# midi-vidi.net
KiCad netlist of a schematic drawn in EAGLE
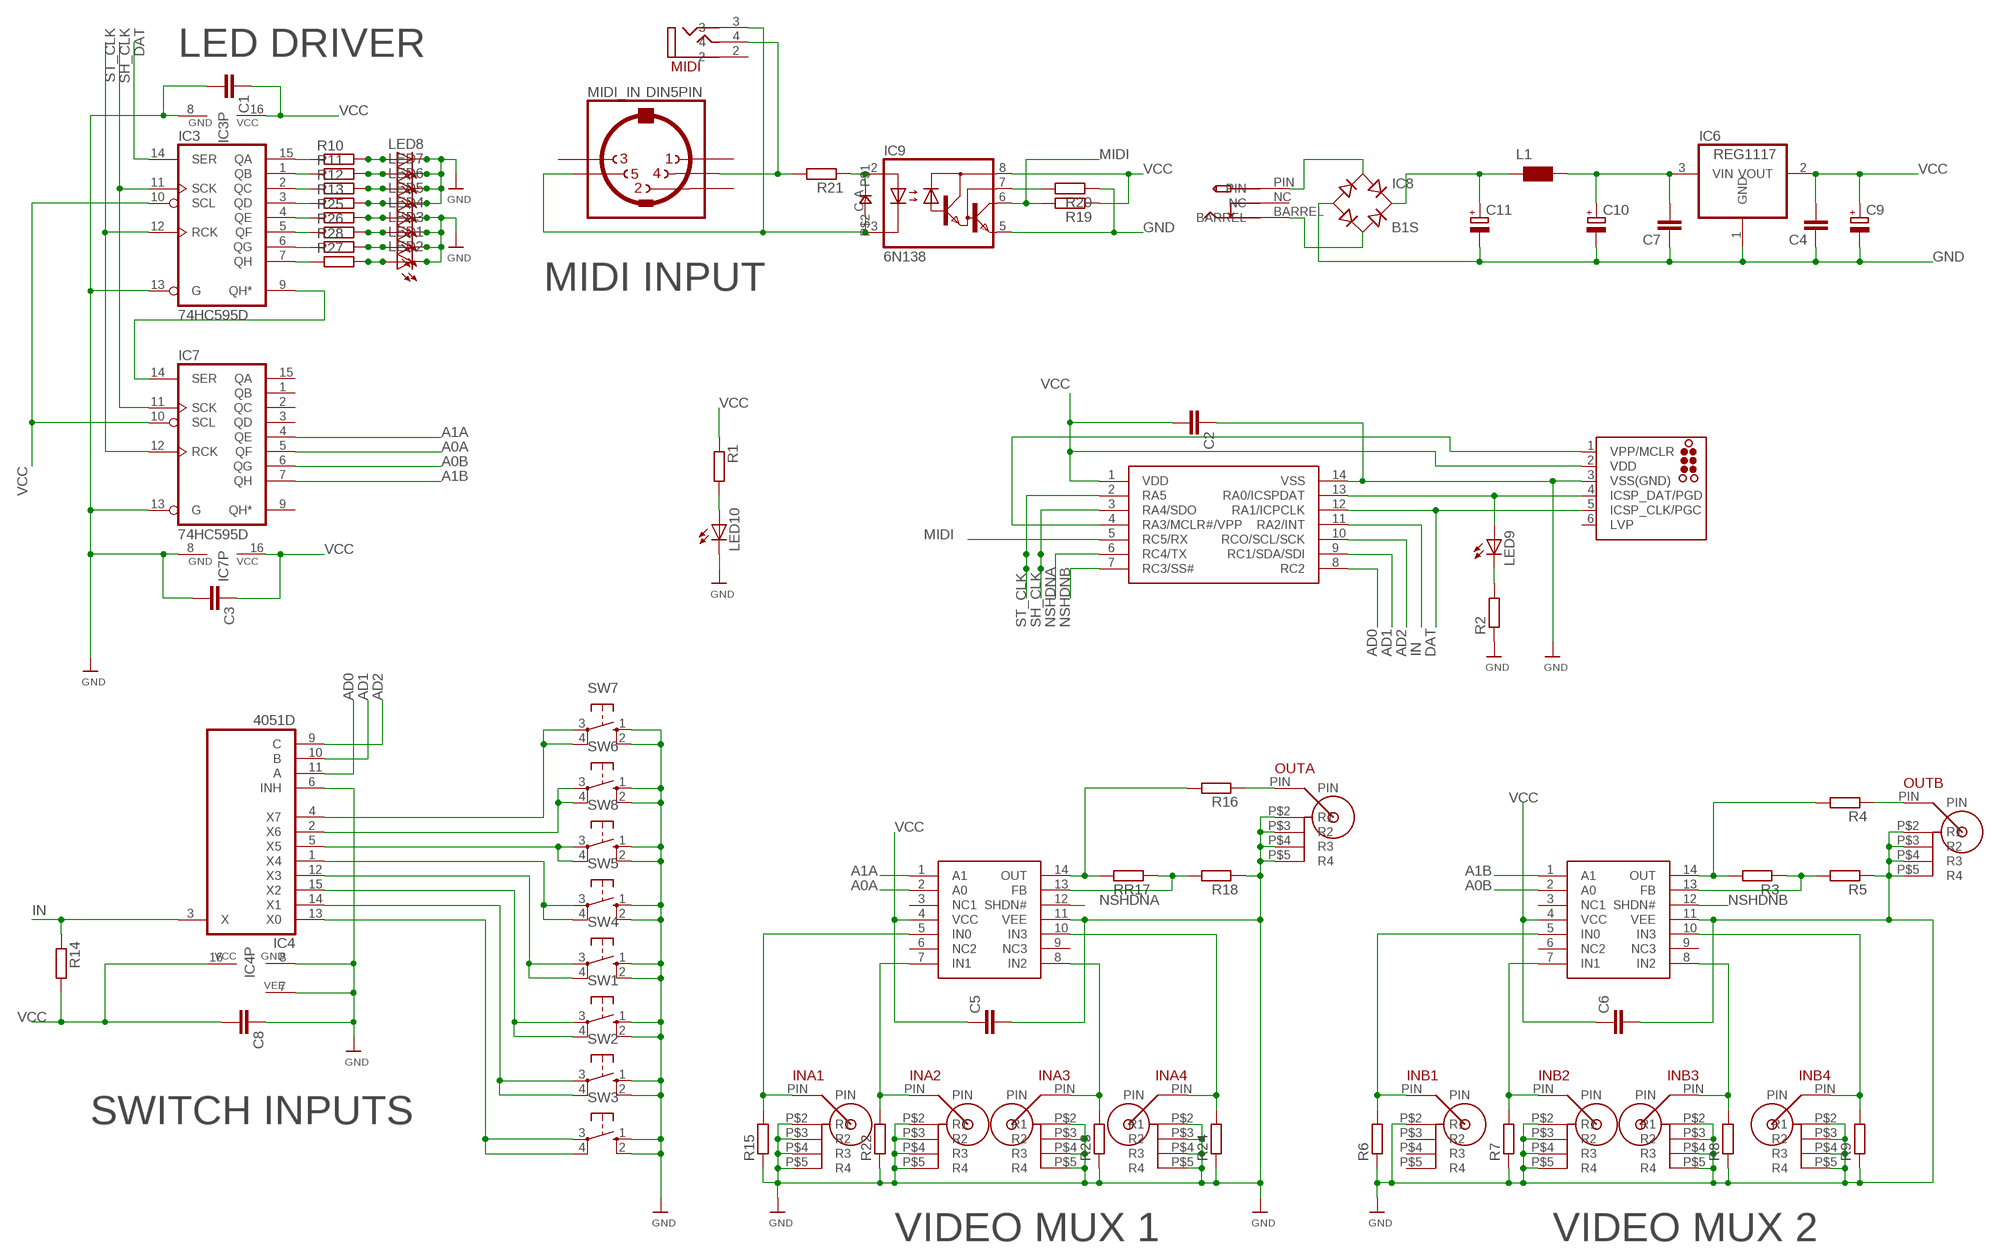
[diagram p0: schematic, sheet 1]

(export (version "E")
  (design (tool "Eeschema 10.0.6"))
  (components
    (comp (ref "C1")
      (value "C-EUC0805")
      (footprint "eagle-import:C0805")
      (libsource (lib "eagle-import") (part "C-EUC0805"))
    )
    (comp (ref "C2")
      (value "C-EUC0805")
      (footprint "eagle-import:C0805")
      (libsource (lib "eagle-import") (part "C-EUC0805"))
    )
    (comp (ref "C3")
      (value "C-EUC0805")
      (footprint "eagle-import:C0805")
      (libsource (lib "eagle-import") (part "C-EUC0805"))
    )
    (comp (ref "C4")
      (value "C-EUC0805")
      (footprint "eagle-import:C0805")
      (libsource (lib "eagle-import") (part "C-EUC0805"))
    )
    (comp (ref "C5")
      (value "C-EUC0805")
      (footprint "eagle-import:C0805")
      (libsource (lib "eagle-import") (part "C-EUC0805"))
    )
    (comp (ref "C6")
      (value "C-EUC0805")
      (footprint "eagle-import:C0805")
      (libsource (lib "eagle-import") (part "C-EUC0805"))
    )
    (comp (ref "C7")
      (value "C-EUC0805")
      (footprint "eagle-import:C0805")
      (libsource (lib "eagle-import") (part "C-EUC0805"))
    )
    (comp (ref "C8")
      (value "C-EUC0805")
      (footprint "eagle-import:C0805")
      (libsource (lib "eagle-import") (part "C-EUC0805"))
    )
    (comp (ref "C9")
      (value "CPOL-EUE2,5-6E")
      (footprint "eagle-import:E2,5-6E")
      (libsource (lib "eagle-import") (part "CPOL-EUE2,5-6E"))
    )
    (comp (ref "C10")
      (value "CPOL-EUE2,5-6E")
      (footprint "eagle-import:E2,5-6E")
      (libsource (lib "eagle-import") (part "CPOL-EUE2,5-6E"))
    )
    (comp (ref "C11")
      (value "CPOL-EUE2,5-6E")
      (footprint "eagle-import:E2,5-6E")
      (libsource (lib "eagle-import") (part "CPOL-EUE2,5-6E"))
    )
    (comp (ref "D1")
      (value "0805DIODE")
      (footprint "eagle-import:0805DIODE")
      (libsource (lib "eagle-import") (part "0805DIODE"))
    )
    (comp (ref "IC1")
      (value "MAX4311SO14")
      (footprint "eagle-import:SO14")
      (libsource (lib "eagle-import") (part "MAX4311SO14"))
    )
    (comp (ref "IC2")
      (value "PIC16F1825SO14")
      (footprint "eagle-import:SO14")
      (libsource (lib "eagle-import") (part "PIC16F1825SO14"))
    )
    (comp (ref "IC3")
      (value "74HC595D")
      (footprint "eagle-import:SO16")
      (libsource (lib "eagle-import") (part "74595DHC"))
    )
    (comp (ref "IC4")
      (value "4051D")
      (footprint "eagle-import:SO16")
      (libsource (lib "eagle-import") (part "4051D"))
    )
    (comp (ref "IC5")
      (value "MAX4311SO14")
      (footprint "eagle-import:SO14")
      (libsource (lib "eagle-import") (part "MAX4311SO14"))
    )
    (comp (ref "IC6")
      (value "REG1117")
      (footprint "eagle-import:SOT223")
      (libsource (lib "eagle-import") (part "REG1117"))
    )
    (comp (ref "IC7")
      (value "74HC595D")
      (footprint "eagle-import:SO16")
      (libsource (lib "eagle-import") (part "74595DHC"))
    )
    (comp (ref "IC8")
      (value "B1S")
      (footprint "eagle-import:MBS")
      (libsource (lib "eagle-import") (part "BS1"))
    )
    (comp (ref "IC9")
      (value "6N138")
      (footprint "eagle-import:DIL08")
      (fields (field (name "MF") "VISHAY/TELEFUNKEN"))
      (libsource (lib "eagle-import") (part "6N138"))
    )
    (comp (ref "ICSP")
      (value "TC2030-MCP-NL")
      (footprint "eagle-import:TC2030-MCP-NL")
      (libsource (lib "eagle-import") (part "TC2030-MCP-NL"))
    )
    (comp (ref "INA1")
      (value "RCAVERT")
      (footprint "eagle-import:RCAVERT")
      (libsource (lib "eagle-import") (part "RCAVERT"))
    )
    (comp (ref "INA2")
      (value "RCAVERT")
      (footprint "eagle-import:RCAVERT")
      (libsource (lib "eagle-import") (part "RCAVERT"))
    )
    (comp (ref "INA3")
      (value "RCAVERT")
      (footprint "eagle-import:RCAVERT")
      (libsource (lib "eagle-import") (part "RCAVERT"))
    )
    (comp (ref "INA4")
      (value "RCAVERT")
      (footprint "eagle-import:RCAVERT")
      (libsource (lib "eagle-import") (part "RCAVERT"))
    )
    (comp (ref "INB1")
      (value "RCAVERT")
      (footprint "eagle-import:RCAVERT")
      (libsource (lib "eagle-import") (part "RCAVERT"))
    )
    (comp (ref "INB2")
      (value "RCAVERT")
      (footprint "eagle-import:RCAVERT")
      (libsource (lib "eagle-import") (part "RCAVERT"))
    )
    (comp (ref "INB3")
      (value "RCAVERT")
      (footprint "eagle-import:RCAVERT")
      (libsource (lib "eagle-import") (part "RCAVERT"))
    )
    (comp (ref "INB4")
      (value "RCAVERT")
      (footprint "eagle-import:RCAVERT")
      (libsource (lib "eagle-import") (part "RCAVERT"))
    )
    (comp (ref "L1")
      (value "WE-TI_L")
      (footprint "eagle-import:WE-TI_L")
      (libsource (lib "eagle-import") (part "WE-TI_L"))
    )
    (comp (ref "LED1")
      (value "LED3MM")
      (footprint "eagle-import:LED3MM")
      (libsource (lib "eagle-import") (part "LED3MM"))
    )
    (comp (ref "LED2")
      (value "LED3MM")
      (footprint "eagle-import:LED3MM")
      (libsource (lib "eagle-import") (part "LED3MM"))
    )
    (comp (ref "LED3")
      (value "LED3MM")
      (footprint "eagle-import:LED3MM")
      (libsource (lib "eagle-import") (part "LED3MM"))
    )
    (comp (ref "LED4")
      (value "LED3MM")
      (footprint "eagle-import:LED3MM")
      (libsource (lib "eagle-import") (part "LED3MM"))
    )
    (comp (ref "LED5")
      (value "LED3MM")
      (footprint "eagle-import:LED3MM")
      (libsource (lib "eagle-import") (part "LED3MM"))
    )
    (comp (ref "LED6")
      (value "LED3MM")
      (footprint "eagle-import:LED3MM")
      (libsource (lib "eagle-import") (part "LED3MM"))
    )
    (comp (ref "LED7")
      (value "LED3MM")
      (footprint "eagle-import:LED3MM")
      (libsource (lib "eagle-import") (part "LED3MM"))
    )
    (comp (ref "LED8")
      (value "LED3MM")
      (footprint "eagle-import:LED3MM")
      (libsource (lib "eagle-import") (part "LED3MM"))
    )
    (comp (ref "LED9")
      (value "LED3MM")
      (footprint "eagle-import:LED3MM")
      (libsource (lib "eagle-import") (part "LED3MM"))
    )
    (comp (ref "LED10")
      (value "LED3MM")
      (footprint "eagle-import:LED3MM")
      (libsource (lib "eagle-import") (part "LED3MM"))
    )
    (comp (ref "MIDI")
      (value "VERTICAL_3_5MM_SOCKET")
      (footprint "eagle-import:VERTICAL_3_5MM_SOCKET")
      (libsource (lib "eagle-import") (part "VERTICAL_3_5MM_SOCKET"))
    )
    (comp (ref "MIDI_IN")
      (value "DIN5PIN")
      (footprint "eagle-import:EDGEDIN")
      (libsource (lib "eagle-import") (part "DIN5PIN"))
    )
    (comp (ref "OUTA")
      (value "RCAVERT")
      (footprint "eagle-import:RCAVERT")
      (libsource (lib "eagle-import") (part "RCAVERT"))
    )
    (comp (ref "OUTB")
      (value "RCAVERT")
      (footprint "eagle-import:RCAVERT")
      (libsource (lib "eagle-import") (part "RCAVERT"))
    )
    (comp (ref "R1")
      (value "R-EU_R0805")
      (footprint "eagle-import:R0805")
      (libsource (lib "eagle-import") (part "R-EU_R0805"))
    )
    (comp (ref "R2")
      (value "R-EU_R0805")
      (footprint "eagle-import:R0805")
      (libsource (lib "eagle-import") (part "R-EU_R0805"))
    )
    (comp (ref "R3")
      (value "R-EU_R0805")
      (footprint "eagle-import:R0805")
      (libsource (lib "eagle-import") (part "R-EU_R0805"))
    )
    (comp (ref "R4")
      (value "R-EU_R0805")
      (footprint "eagle-import:R0805")
      (libsource (lib "eagle-import") (part "R-EU_R0805"))
    )
    (comp (ref "R5")
      (value "R-EU_R0805")
      (footprint "eagle-import:R0805")
      (libsource (lib "eagle-import") (part "R-EU_R0805"))
    )
    (comp (ref "R6")
      (value "R-EU_R0805")
      (footprint "eagle-import:R0805")
      (libsource (lib "eagle-import") (part "R-EU_R0805"))
    )
    (comp (ref "R7")
      (value "R-EU_R0805")
      (footprint "eagle-import:R0805")
      (libsource (lib "eagle-import") (part "R-EU_R0805"))
    )
    (comp (ref "R8")
      (value "R-EU_R0805")
      (footprint "eagle-import:R0805")
      (libsource (lib "eagle-import") (part "R-EU_R0805"))
    )
    (comp (ref "R9")
      (value "R-EU_R0805")
      (footprint "eagle-import:R0805")
      (libsource (lib "eagle-import") (part "R-EU_R0805"))
    )
    (comp (ref "R10")
      (value "R-EU_R0805")
      (footprint "eagle-import:R0805")
      (libsource (lib "eagle-import") (part "R-EU_R0805"))
    )
    (comp (ref "R11")
      (value "R-EU_R0805")
      (footprint "eagle-import:R0805")
      (libsource (lib "eagle-import") (part "R-EU_R0805"))
    )
    (comp (ref "R12")
      (value "R-EU_R0805")
      (footprint "eagle-import:R0805")
      (libsource (lib "eagle-import") (part "R-EU_R0805"))
    )
    (comp (ref "R13")
      (value "R-EU_R0805")
      (footprint "eagle-import:R0805")
      (libsource (lib "eagle-import") (part "R-EU_R0805"))
    )
    (comp (ref "R14")
      (value "R-EU_R0805")
      (footprint "eagle-import:R0805")
      (libsource (lib "eagle-import") (part "R-EU_R0805"))
    )
    (comp (ref "R15")
      (value "R-EU_R0805")
      (footprint "eagle-import:R0805")
      (libsource (lib "eagle-import") (part "R-EU_R0805"))
    )
    (comp (ref "R16")
      (value "R-EU_R0805")
      (footprint "eagle-import:R0805")
      (libsource (lib "eagle-import") (part "R-EU_R0805"))
    )
    (comp (ref "R18")
      (value "R-EU_R0805")
      (footprint "eagle-import:R0805")
      (libsource (lib "eagle-import") (part "R-EU_R0805"))
    )
    (comp (ref "R19")
      (value "R-EU_R0805")
      (footprint "eagle-import:R0805")
      (libsource (lib "eagle-import") (part "R-EU_R0805"))
    )
    (comp (ref "R20")
      (value "R-EU_R0805")
      (footprint "eagle-import:R0805")
      (libsource (lib "eagle-import") (part "R-EU_R0805"))
    )
    (comp (ref "R21")
      (value "R-EU_R0805")
      (footprint "eagle-import:R0805")
      (libsource (lib "eagle-import") (part "R-EU_R0805"))
    )
    (comp (ref "R22")
      (value "R-EU_R0805")
      (footprint "eagle-import:R0805")
      (libsource (lib "eagle-import") (part "R-EU_R0805"))
    )
    (comp (ref "R23")
      (value "R-EU_R0805")
      (footprint "eagle-import:R0805")
      (libsource (lib "eagle-import") (part "R-EU_R0805"))
    )
    (comp (ref "R24")
      (value "R-EU_R0805")
      (footprint "eagle-import:R0805")
      (libsource (lib "eagle-import") (part "R-EU_R0805"))
    )
    (comp (ref "R25")
      (value "R-EU_R0805")
      (footprint "eagle-import:R0805")
      (libsource (lib "eagle-import") (part "R-EU_R0805"))
    )
    (comp (ref "R26")
      (value "R-EU_R0805")
      (footprint "eagle-import:R0805")
      (libsource (lib "eagle-import") (part "R-EU_R0805"))
    )
    (comp (ref "R27")
      (value "R-EU_R0805")
      (footprint "eagle-import:R0805")
      (libsource (lib "eagle-import") (part "R-EU_R0805"))
    )
    (comp (ref "R28")
      (value "R-EU_R0805")
      (footprint "eagle-import:R0805")
      (libsource (lib "eagle-import") (part "R-EU_R0805"))
    )
    (comp (ref "RR17")
      (value "R-EU_R0805")
      (footprint "eagle-import:R0805")
      (libsource (lib "eagle-import") (part "R-EU_R0805"))
    )
    (comp (ref "SW1")
      (value "10-XX")
      (footprint "eagle-import:B3F-10XX")
      (fields (field (name "MPN") "B3F-1000"))
      (libsource (lib "eagle-import") (part "10-XX"))
    )
    (comp (ref "SW2")
      (value "10-XX")
      (footprint "eagle-import:B3F-10XX")
      (fields (field (name "MPN") "B3F-1000"))
      (libsource (lib "eagle-import") (part "10-XX"))
    )
    (comp (ref "SW3")
      (value "10-XX")
      (footprint "eagle-import:B3F-10XX")
      (fields (field (name "MPN") "B3F-1000"))
      (libsource (lib "eagle-import") (part "10-XX"))
    )
    (comp (ref "SW4")
      (value "10-XX")
      (footprint "eagle-import:B3F-10XX")
      (fields (field (name "MPN") "B3F-1000"))
      (libsource (lib "eagle-import") (part "10-XX"))
    )
    (comp (ref "SW5")
      (value "10-XX")
      (footprint "eagle-import:B3F-10XX")
      (fields (field (name "MPN") "B3F-1000"))
      (libsource (lib "eagle-import") (part "10-XX"))
    )
    (comp (ref "SW6")
      (value "10-XX")
      (footprint "eagle-import:B3F-10XX")
      (fields (field (name "MPN") "B3F-1000"))
      (libsource (lib "eagle-import") (part "10-XX"))
    )
    (comp (ref "SW7")
      (value "10-XX")
      (footprint "eagle-import:B3F-10XX")
      (fields (field (name "MPN") "B3F-1000"))
      (libsource (lib "eagle-import") (part "10-XX"))
    )
    (comp (ref "SW8")
      (value "10-XX")
      (footprint "eagle-import:B3F-10XX")
      (fields (field (name "MPN") "B3F-1000"))
      (libsource (lib "eagle-import") (part "10-XX"))
    )
    (comp (ref "U$2")
      (value "PWR_SOCKET_2_1MM")
      (footprint "eagle-import:PWR_SOCKET_2_1MM")
      (libsource (lib "eagle-import") (part "PWR_SOCKET_2_1MM"))
    )
  )
  (nets
    (net (code "1") (name "/A0A") (class "Default")
      (node (ref "IC5") (pin "2") (pinfunction "A0_2") (pintype "bidirectional"))
      (node (ref "IC7") (pin "5") (pinfunction "QF_5") (pintype "tri_state"))
    )
    (net (code "2") (name "/A0B") (class "Default")
      (node (ref "IC1") (pin "2") (pinfunction "A0_2") (pintype "bidirectional"))
      (node (ref "IC7") (pin "6") (pinfunction "QG_6") (pintype "tri_state"))
    )
    (net (code "3") (name "/A1A") (class "Default")
      (node (ref "IC5") (pin "1") (pinfunction "A1_1") (pintype "bidirectional"))
      (node (ref "IC7") (pin "4") (pinfunction "QE_4") (pintype "tri_state"))
    )
    (net (code "4") (name "/A1B") (class "Default")
      (node (ref "IC1") (pin "1") (pinfunction "A1_1") (pintype "bidirectional"))
      (node (ref "IC7") (pin "7") (pinfunction "QH_7") (pintype "tri_state"))
    )
    (net (code "5") (name "/AD0") (class "Default")
      (node (ref "IC2") (pin "8") (pinfunction "RC2_8") (pintype "bidirectional"))
      (node (ref "IC4") (pin "11") (pinfunction "A_11") (pintype "input"))
    )
    (net (code "6") (name "/AD1") (class "Default")
      (node (ref "IC2") (pin "9") (pinfunction "RC1/SDA/SDI_9") (pintype "bidirectional"))
      (node (ref "IC4") (pin "10") (pinfunction "B_10") (pintype "input"))
    )
    (net (code "7") (name "/AD2") (class "Default")
      (node (ref "IC2") (pin "10") (pinfunction "RCO/SCL/SCK_10") (pintype "bidirectional"))
      (node (ref "IC4") (pin "9") (pinfunction "C_9") (pintype "input"))
    )
    (net (code "8") (name "/DAT") (class "Default")
      (node (ref "IC2") (pin "12") (pinfunction "RA1/ICPCLK_12") (pintype "bidirectional"))
      (node (ref "IC3") (pin "14") (pinfunction "SER_14") (pintype "input"))
      (node (ref "ICSP") (pin "5") (pinfunction "ICSP_CLK/PGC_5") (pintype "output"))
    )
    (net (code "9") (name "/IN") (class "Default")
      (node (ref "IC2") (pin "11") (pinfunction "RA2/INT_11") (pintype "bidirectional"))
      (node (ref "IC4") (pin "3") (pinfunction "X_3") (pintype "bidirectional"))
      (node (ref "R14") (pin "1") (pinfunction "1_1") (pintype "passive"))
    )
    (net (code "10") (name "/MIDI") (class "Default")
      (node (ref "IC2") (pin "5") (pinfunction "RC5/RX_5") (pintype "bidirectional"))
      (node (ref "IC9") (pin "6") (pinfunction "VO_6") (pintype "passive"))
      (node (ref "R19") (pin "2") (pinfunction "2_2") (pintype "passive"))
    )
    (net (code "11") (name "/NSHDNA") (class "Default")
      (node (ref "IC2") (pin "6") (pinfunction "RC4/TX_6") (pintype "bidirectional"))
      (node (ref "IC5") (pin "12") (pinfunction "SHDN#_12") (pintype "bidirectional"))
    )
    (net (code "12") (name "/NSHDNB") (class "Default")
      (node (ref "IC1") (pin "12") (pinfunction "SHDN#_12") (pintype "bidirectional"))
      (node (ref "IC2") (pin "7") (pinfunction "RC3/SS#_7") (pintype "bidirectional"))
    )
    (net (code "13") (name "/SH_CLK") (class "Default")
      (node (ref "IC2") (pin "3") (pinfunction "RA4/SDO_3") (pintype "bidirectional"))
      (node (ref "IC3") (pin "11") (pinfunction "SCK_11") (pintype "input"))
      (node (ref "IC7") (pin "11") (pinfunction "SCK_11") (pintype "input"))
    )
    (net (code "14") (name "/ST_CLK") (class "Default")
      (node (ref "IC2") (pin "2") (pinfunction "RA5_2") (pintype "bidirectional"))
      (node (ref "IC3") (pin "12") (pinfunction "RCK_12") (pintype "input"))
      (node (ref "IC7") (pin "12") (pinfunction "RCK_12") (pintype "input"))
    )
    (net (code "15") (name "/VCC") (class "Default")
      (node (ref "C1") (pin "1") (pinfunction "1_1") (pintype "passive"))
      (node (ref "C2") (pin "2") (pinfunction "2_2") (pintype "passive"))
      (node (ref "C3") (pin "1") (pinfunction "1_1") (pintype "passive"))
      (node (ref "C4") (pin "2") (pinfunction "2_2") (pintype "passive"))
      (node (ref "C5") (pin "1") (pinfunction "1_1") (pintype "passive"))
      (node (ref "C6") (pin "1") (pinfunction "1_1") (pintype "passive"))
      (node (ref "C8") (pin "2") (pinfunction "2_2") (pintype "passive"))
      (node (ref "C9") (pin "+") (pinfunction "+_+") (pintype "passive"))
      (node (ref "IC1") (pin "4") (pinfunction "VCC_4") (pintype "bidirectional"))
      (node (ref "IC2") (pin "1") (pinfunction "VDD_1") (pintype "power_in"))
      (node (ref "IC3") (pin "10") (pinfunction "SCL_10") (pintype "input"))
      (node (ref "IC3") (pin "16") (pinfunction "VCC_16") (pintype "power_in"))
      (node (ref "IC4") (pin "16") (pinfunction "VCC_16") (pintype "power_in"))
      (node (ref "IC5") (pin "4") (pinfunction "VCC_4") (pintype "bidirectional"))
      (node (ref "IC6") (pin "2") (pinfunction "VOUT_2") (pintype "output"))
      (node (ref "IC7") (pin "10") (pinfunction "SCL_10") (pintype "input"))
      (node (ref "IC7") (pin "16") (pinfunction "VCC_16") (pintype "power_in"))
      (node (ref "IC9") (pin "8") (pinfunction "VCC_8") (pintype "passive"))
      (node (ref "ICSP") (pin "2") (pinfunction "VDD_2") (pintype "power_in"))
      (node (ref "R1") (pin "1") (pinfunction "1_1") (pintype "passive"))
      (node (ref "R14") (pin "2") (pinfunction "2_2") (pintype "passive"))
      (node (ref "R19") (pin "1") (pinfunction "1_1") (pintype "passive"))
    )
    (net (code "16") (name "GND") (class "Default")
      (node (ref "C1") (pin "2") (pinfunction "2_2") (pintype "passive"))
      (node (ref "C10") (pin "-") (pinfunction "-_-") (pintype "passive"))
      (node (ref "C11") (pin "-") (pinfunction "-_-") (pintype "passive"))
      (node (ref "C2") (pin "1") (pinfunction "1_1") (pintype "passive"))
      (node (ref "C3") (pin "2") (pinfunction "2_2") (pintype "passive"))
      (node (ref "C4") (pin "1") (pinfunction "1_1") (pintype "passive"))
      (node (ref "C5") (pin "2") (pinfunction "2_2") (pintype "passive"))
      (node (ref "C6") (pin "2") (pinfunction "2_2") (pintype "passive"))
      (node (ref "C7") (pin "1") (pinfunction "1_1") (pintype "passive"))
      (node (ref "C8") (pin "1") (pinfunction "1_1") (pintype "passive"))
      (node (ref "C9") (pin "-") (pinfunction "-_-") (pintype "passive"))
      (node (ref "IC1") (pin "11") (pinfunction "VEE_11") (pintype "bidirectional"))
      (node (ref "IC2") (pin "14") (pinfunction "VSS_14") (pintype "power_in"))
      (node (ref "IC3") (pin "13") (pinfunction "G_13") (pintype "input"))
      (node (ref "IC3") (pin "8") (pinfunction "GND_8") (pintype "power_in"))
      (node (ref "IC4") (pin "6") (pinfunction "INH_6") (pintype "input"))
      (node (ref "IC4") (pin "7") (pinfunction "VEE_7") (pintype "power_in"))
      (node (ref "IC4") (pin "8") (pinfunction "GND_8") (pintype "power_in"))
      (node (ref "IC5") (pin "11") (pinfunction "VEE_11") (pintype "bidirectional"))
      (node (ref "IC6") (pin "1") (pinfunction "GND_1") (pintype "power_in"))
      (node (ref "IC7") (pin "13") (pinfunction "G_13") (pintype "input"))
      (node (ref "IC7") (pin "8") (pinfunction "GND_8") (pintype "power_in"))
      (node (ref "IC8") (pin "-") (pinfunction "-_-") (pintype "passive"))
      (node (ref "IC9") (pin "5") (pinfunction "GND_5") (pintype "passive"))
      (node (ref "ICSP") (pin "3") (pinfunction "VSS(GND)_3") (pintype "power_in"))
      (node (ref "INA1") (pin "P$2") (pinfunction "R1_P$2") (pintype "bidirectional"))
      (node (ref "INA1") (pin "P$3") (pinfunction "R2_P$3") (pintype "bidirectional"))
      (node (ref "INA1") (pin "P$4") (pinfunction "R3_P$4") (pintype "bidirectional"))
      (node (ref "INA1") (pin "P$5") (pinfunction "R4_P$5") (pintype "bidirectional"))
      (node (ref "INA2") (pin "P$2") (pinfunction "R1_P$2") (pintype "bidirectional"))
      (node (ref "INA2") (pin "P$3") (pinfunction "R2_P$3") (pintype "bidirectional"))
      (node (ref "INA2") (pin "P$4") (pinfunction "R3_P$4") (pintype "bidirectional"))
      (node (ref "INA2") (pin "P$5") (pinfunction "R4_P$5") (pintype "bidirectional"))
      (node (ref "INA3") (pin "P$2") (pinfunction "R1_P$2") (pintype "bidirectional"))
      (node (ref "INA3") (pin "P$3") (pinfunction "R2_P$3") (pintype "bidirectional"))
      (node (ref "INA3") (pin "P$4") (pinfunction "R3_P$4") (pintype "bidirectional"))
      (node (ref "INA3") (pin "P$5") (pinfunction "R4_P$5") (pintype "bidirectional"))
      (node (ref "INA4") (pin "P$2") (pinfunction "R1_P$2") (pintype "bidirectional"))
      (node (ref "INA4") (pin "P$3") (pinfunction "R2_P$3") (pintype "bidirectional"))
      (node (ref "INA4") (pin "P$4") (pinfunction "R3_P$4") (pintype "bidirectional"))
      (node (ref "INA4") (pin "P$5") (pinfunction "R4_P$5") (pintype "bidirectional"))
      (node (ref "INB1") (pin "P$2") (pinfunction "R1_P$2") (pintype "bidirectional"))
      (node (ref "INB2") (pin "P$2") (pinfunction "R1_P$2") (pintype "bidirectional"))
      (node (ref "INB2") (pin "P$3") (pinfunction "R2_P$3") (pintype "bidirectional"))
      (node (ref "INB2") (pin "P$4") (pinfunction "R3_P$4") (pintype "bidirectional"))
      (node (ref "INB2") (pin "P$5") (pinfunction "R4_P$5") (pintype "bidirectional"))
      (node (ref "INB3") (pin "P$2") (pinfunction "R1_P$2") (pintype "bidirectional"))
      (node (ref "INB3") (pin "P$3") (pinfunction "R2_P$3") (pintype "bidirectional"))
      (node (ref "INB3") (pin "P$4") (pinfunction "R3_P$4") (pintype "bidirectional"))
      (node (ref "INB3") (pin "P$5") (pinfunction "R4_P$5") (pintype "bidirectional"))
      (node (ref "INB4") (pin "P$2") (pinfunction "R1_P$2") (pintype "bidirectional"))
      (node (ref "INB4") (pin "P$3") (pinfunction "R2_P$3") (pintype "bidirectional"))
      (node (ref "INB4") (pin "P$4") (pinfunction "R3_P$4") (pintype "bidirectional"))
      (node (ref "INB4") (pin "P$5") (pinfunction "R4_P$5") (pintype "bidirectional"))
      (node (ref "LED1") (pin "K") (pinfunction "C_K") (pintype "passive"))
      (node (ref "LED10") (pin "K") (pinfunction "C_K") (pintype "passive"))
      (node (ref "LED2") (pin "K") (pinfunction "C_K") (pintype "passive"))
      (node (ref "LED3") (pin "K") (pinfunction "C_K") (pintype "passive"))
      (node (ref "LED4") (pin "K") (pinfunction "C_K") (pintype "passive"))
      (node (ref "LED5") (pin "K") (pinfunction "C_K") (pintype "passive"))
      (node (ref "LED6") (pin "K") (pinfunction "C_K") (pintype "passive"))
      (node (ref "LED7") (pin "K") (pinfunction "C_K") (pintype "passive"))
      (node (ref "LED8") (pin "K") (pinfunction "C_K") (pintype "passive"))
      (node (ref "OUTA") (pin "P$2") (pinfunction "R1_P$2") (pintype "bidirectional"))
      (node (ref "OUTA") (pin "P$3") (pinfunction "R2_P$3") (pintype "bidirectional"))
      (node (ref "OUTA") (pin "P$4") (pinfunction "R3_P$4") (pintype "bidirectional"))
      (node (ref "OUTA") (pin "P$5") (pinfunction "R4_P$5") (pintype "bidirectional"))
      (node (ref "OUTB") (pin "P$2") (pinfunction "R1_P$2") (pintype "bidirectional"))
      (node (ref "OUTB") (pin "P$3") (pinfunction "R2_P$3") (pintype "bidirectional"))
      (node (ref "OUTB") (pin "P$4") (pinfunction "R3_P$4") (pintype "bidirectional"))
      (node (ref "OUTB") (pin "P$5") (pinfunction "R4_P$5") (pintype "bidirectional"))
      (node (ref "R15") (pin "1") (pinfunction "1_1") (pintype "passive"))
      (node (ref "R18") (pin "1") (pinfunction "1_1") (pintype "passive"))
      (node (ref "R2") (pin "1") (pinfunction "1_1") (pintype "passive"))
      (node (ref "R20") (pin "1") (pinfunction "1_1") (pintype "passive"))
      (node (ref "R22") (pin "1") (pinfunction "1_1") (pintype "passive"))
      (node (ref "R23") (pin "1") (pinfunction "1_1") (pintype "passive"))
      (node (ref "R24") (pin "1") (pinfunction "1_1") (pintype "passive"))
      (node (ref "R5") (pin "1") (pinfunction "1_1") (pintype "passive"))
      (node (ref "R6") (pin "1") (pinfunction "1_1") (pintype "passive"))
      (node (ref "R7") (pin "1") (pinfunction "1_1") (pintype "passive"))
      (node (ref "R8") (pin "1") (pinfunction "1_1") (pintype "passive"))
      (node (ref "R9") (pin "1") (pinfunction "1_1") (pintype "passive"))
      (node (ref "SW1") (pin "1") (pinfunction "S_1") (pintype "passive"))
      (node (ref "SW1") (pin "2") (pinfunction "S1_2") (pintype "passive"))
      (node (ref "SW2") (pin "1") (pinfunction "S_1") (pintype "passive"))
      (node (ref "SW2") (pin "2") (pinfunction "S1_2") (pintype "passive"))
      (node (ref "SW3") (pin "1") (pinfunction "S_1") (pintype "passive"))
      (node (ref "SW3") (pin "2") (pinfunction "S1_2") (pintype "passive"))
      (node (ref "SW4") (pin "1") (pinfunction "S_1") (pintype "passive"))
      (node (ref "SW4") (pin "2") (pinfunction "S1_2") (pintype "passive"))
      (node (ref "SW5") (pin "1") (pinfunction "S_1") (pintype "passive"))
      (node (ref "SW5") (pin "2") (pinfunction "S1_2") (pintype "passive"))
      (node (ref "SW6") (pin "1") (pinfunction "S_1") (pintype "passive"))
      (node (ref "SW6") (pin "2") (pinfunction "S1_2") (pintype "passive"))
      (node (ref "SW7") (pin "1") (pinfunction "S_1") (pintype "passive"))
      (node (ref "SW7") (pin "2") (pinfunction "S1_2") (pintype "passive"))
      (node (ref "SW8") (pin "1") (pinfunction "S_1") (pintype "passive"))
      (node (ref "SW8") (pin "2") (pinfunction "S1_2") (pintype "passive"))
    )
    (net (code "17") (name "Net-(D1-P$1)") (class "Default")
      (node (ref "D1") (pin "C") (pinfunction "P$1_C") (pintype "bidirectional"))
      (node (ref "IC9") (pin "3") (pinfunction "C_3") (pintype "passive"))
      (node (ref "MIDI") (pin "3") (pinfunction "3_3") (pintype "bidirectional"))
      (node (ref "MIDI_IN") (pin "5") (pinfunction "5_5") (pintype "passive"))
    )
    (net (code "18") (name "Net-(D1-P$2)") (class "Default")
      (node (ref "D1") (pin "A") (pinfunction "P$2_A") (pintype "bidirectional"))
      (node (ref "IC9") (pin "2") (pinfunction "A_2") (pintype "passive"))
      (node (ref "R21") (pin "1") (pinfunction "1_1") (pintype "passive"))
    )
    (net (code "19") (name "Net-(IC1-FB)") (class "Default")
      (node (ref "IC1") (pin "13") (pinfunction "FB_13") (pintype "bidirectional"))
      (node (ref "R3") (pin "1") (pinfunction "1_1") (pintype "passive"))
      (node (ref "R5") (pin "2") (pinfunction "2_2") (pintype "passive"))
    )
    (net (code "20") (name "Net-(IC1-IN0)") (class "Default")
      (node (ref "IC1") (pin "5") (pinfunction "IN0_5") (pintype "bidirectional"))
      (node (ref "INB1") (pin "PIN") (pinfunction "PIN_PIN") (pintype "bidirectional"))
      (node (ref "R6") (pin "2") (pinfunction "2_2") (pintype "passive"))
    )
    (net (code "21") (name "Net-(IC1-IN1)") (class "Default")
      (node (ref "IC1") (pin "7") (pinfunction "IN1_7") (pintype "bidirectional"))
      (node (ref "INB2") (pin "PIN") (pinfunction "PIN_PIN") (pintype "bidirectional"))
      (node (ref "R7") (pin "2") (pinfunction "2_2") (pintype "passive"))
    )
    (net (code "22") (name "Net-(IC1-IN2)") (class "Default")
      (node (ref "IC1") (pin "8") (pinfunction "IN2_8") (pintype "bidirectional"))
      (node (ref "INB3") (pin "PIN") (pinfunction "PIN_PIN") (pintype "bidirectional"))
      (node (ref "R8") (pin "2") (pinfunction "2_2") (pintype "passive"))
    )
    (net (code "23") (name "Net-(IC1-IN3)") (class "Default")
      (node (ref "IC1") (pin "10") (pinfunction "IN3_10") (pintype "bidirectional"))
      (node (ref "INB4") (pin "PIN") (pinfunction "PIN_PIN") (pintype "bidirectional"))
      (node (ref "R9") (pin "2") (pinfunction "2_2") (pintype "passive"))
    )
    (net (code "24") (name "Net-(IC1-OUT)") (class "Default")
      (node (ref "IC1") (pin "14") (pinfunction "OUT_14") (pintype "bidirectional"))
      (node (ref "R3") (pin "2") (pinfunction "2_2") (pintype "passive"))
      (node (ref "R4") (pin "2") (pinfunction "2_2") (pintype "passive"))
    )
    (net (code "25") (name "Net-(IC2-RA0{slash}ICSPDAT)") (class "Default")
      (node (ref "IC2") (pin "13") (pinfunction "RA0/ICSPDAT_13") (pintype "bidirectional"))
      (node (ref "ICSP") (pin "4") (pinfunction "ICSP_DAT/PGD_4") (pintype "bidirectional"))
      (node (ref "LED9") (pin "A") (pinfunction "A_A") (pintype "passive"))
    )
    (net (code "26") (name "Net-(IC2-RA3{slash}MCLR#{slash}VPP)") (class "Default")
      (node (ref "IC2") (pin "4") (pinfunction "RA3/MCLR#/VPP_4") (pintype "input"))
      (node (ref "ICSP") (pin "1") (pinfunction "VPP/MCLR_1") (pintype "passive"))
    )
    (net (code "27") (name "Net-(IC3A-QA)") (class "Default")
      (node (ref "IC3") (pin "15") (pinfunction "QA_15") (pintype "tri_state"))
      (node (ref "R10") (pin "1") (pinfunction "1_1") (pintype "passive"))
    )
    (net (code "28") (name "Net-(IC3A-QB)") (class "Default")
      (node (ref "IC3") (pin "1") (pinfunction "QB_1") (pintype "tri_state"))
      (node (ref "R11") (pin "1") (pinfunction "1_1") (pintype "passive"))
    )
    (net (code "29") (name "Net-(IC3A-QC)") (class "Default")
      (node (ref "IC3") (pin "2") (pinfunction "QC_2") (pintype "tri_state"))
      (node (ref "R12") (pin "1") (pinfunction "1_1") (pintype "passive"))
    )
    (net (code "30") (name "Net-(IC3A-QD)") (class "Default")
      (node (ref "IC3") (pin "3") (pinfunction "QD_3") (pintype "tri_state"))
      (node (ref "R13") (pin "1") (pinfunction "1_1") (pintype "passive"))
    )
    (net (code "31") (name "Net-(IC3A-QE)") (class "Default")
      (node (ref "IC3") (pin "4") (pinfunction "QE_4") (pintype "tri_state"))
      (node (ref "R25") (pin "1") (pinfunction "1_1") (pintype "passive"))
    )
    (net (code "32") (name "Net-(IC3A-QF)") (class "Default")
      (node (ref "IC3") (pin "5") (pinfunction "QF_5") (pintype "tri_state"))
      (node (ref "R26") (pin "1") (pinfunction "1_1") (pintype "passive"))
    )
    (net (code "33") (name "Net-(IC3A-QG)") (class "Default")
      (node (ref "IC3") (pin "6") (pinfunction "QG_6") (pintype "tri_state"))
      (node (ref "R28") (pin "1") (pinfunction "1_1") (pintype "passive"))
    )
    (net (code "34") (name "Net-(IC3A-QH)") (class "Default")
      (node (ref "IC3") (pin "7") (pinfunction "QH_7") (pintype "tri_state"))
      (node (ref "R27") (pin "1") (pinfunction "1_1") (pintype "passive"))
    )
    (net (code "35") (name "Net-(IC3A-QH*)") (class "Default")
      (node (ref "IC3") (pin "9") (pinfunction "QH*_9") (pintype "tri_state"))
      (node (ref "IC7") (pin "14") (pinfunction "SER_14") (pintype "input"))
    )
    (net (code "36") (name "Net-(IC4A-X0)") (class "Default")
      (node (ref "IC4") (pin "13") (pinfunction "X0_13") (pintype "bidirectional"))
      (node (ref "SW3") (pin "3") (pinfunction "P_3") (pintype "passive"))
      (node (ref "SW3") (pin "4") (pinfunction "P1_4") (pintype "passive"))
    )
    (net (code "37") (name "Net-(IC4A-X1)") (class "Default")
      (node (ref "IC4") (pin "14") (pinfunction "X1_14") (pintype "bidirectional"))
      (node (ref "SW2") (pin "3") (pinfunction "P_3") (pintype "passive"))
      (node (ref "SW2") (pin "4") (pinfunction "P1_4") (pintype "passive"))
    )
    (net (code "38") (name "Net-(IC4A-X2)") (class "Default")
      (node (ref "IC4") (pin "15") (pinfunction "X2_15") (pintype "bidirectional"))
      (node (ref "SW1") (pin "3") (pinfunction "P_3") (pintype "passive"))
      (node (ref "SW1") (pin "4") (pinfunction "P1_4") (pintype "passive"))
    )
    (net (code "39") (name "Net-(IC4A-X3)") (class "Default")
      (node (ref "IC4") (pin "12") (pinfunction "X3_12") (pintype "bidirectional"))
      (node (ref "SW4") (pin "3") (pinfunction "P_3") (pintype "passive"))
      (node (ref "SW4") (pin "4") (pinfunction "P1_4") (pintype "passive"))
    )
    (net (code "40") (name "Net-(IC4A-X4)") (class "Default")
      (node (ref "IC4") (pin "1") (pinfunction "X4_1") (pintype "bidirectional"))
      (node (ref "SW5") (pin "3") (pinfunction "P_3") (pintype "passive"))
      (node (ref "SW5") (pin "4") (pinfunction "P1_4") (pintype "passive"))
    )
    (net (code "41") (name "Net-(IC4A-X5)") (class "Default")
      (node (ref "IC4") (pin "5") (pinfunction "X5_5") (pintype "bidirectional"))
      (node (ref "SW8") (pin "3") (pinfunction "P_3") (pintype "passive"))
      (node (ref "SW8") (pin "4") (pinfunction "P1_4") (pintype "passive"))
    )
    (net (code "42") (name "Net-(IC4A-X6)") (class "Default")
      (node (ref "IC4") (pin "2") (pinfunction "X6_2") (pintype "bidirectional"))
      (node (ref "SW6") (pin "3") (pinfunction "P_3") (pintype "passive"))
      (node (ref "SW6") (pin "4") (pinfunction "P1_4") (pintype "passive"))
    )
    (net (code "43") (name "Net-(IC4A-X7)") (class "Default")
      (node (ref "IC4") (pin "4") (pinfunction "X7_4") (pintype "bidirectional"))
      (node (ref "SW7") (pin "3") (pinfunction "P_3") (pintype "passive"))
      (node (ref "SW7") (pin "4") (pinfunction "P1_4") (pintype "passive"))
    )
    (net (code "44") (name "Net-(IC5-FB)") (class "Default")
      (node (ref "IC5") (pin "13") (pinfunction "FB_13") (pintype "bidirectional"))
      (node (ref "R18") (pin "2") (pinfunction "2_2") (pintype "passive"))
      (node (ref "RR17") (pin "1") (pinfunction "1_1") (pintype "passive"))
    )
    (net (code "45") (name "Net-(IC5-IN0)") (class "Default")
      (node (ref "IC5") (pin "5") (pinfunction "IN0_5") (pintype "bidirectional"))
      (node (ref "INA1") (pin "PIN") (pinfunction "PIN_PIN") (pintype "bidirectional"))
      (node (ref "R15") (pin "2") (pinfunction "2_2") (pintype "passive"))
    )
    (net (code "46") (name "Net-(IC5-IN1)") (class "Default")
      (node (ref "IC5") (pin "7") (pinfunction "IN1_7") (pintype "bidirectional"))
      (node (ref "INA2") (pin "PIN") (pinfunction "PIN_PIN") (pintype "bidirectional"))
      (node (ref "R22") (pin "2") (pinfunction "2_2") (pintype "passive"))
    )
    (net (code "47") (name "Net-(IC5-IN2)") (class "Default")
      (node (ref "IC5") (pin "8") (pinfunction "IN2_8") (pintype "bidirectional"))
      (node (ref "INA3") (pin "PIN") (pinfunction "PIN_PIN") (pintype "bidirectional"))
      (node (ref "R23") (pin "2") (pinfunction "2_2") (pintype "passive"))
    )
    (net (code "48") (name "Net-(IC5-IN3)") (class "Default")
      (node (ref "IC5") (pin "10") (pinfunction "IN3_10") (pintype "bidirectional"))
      (node (ref "INA4") (pin "PIN") (pinfunction "PIN_PIN") (pintype "bidirectional"))
      (node (ref "R24") (pin "2") (pinfunction "2_2") (pintype "passive"))
    )
    (net (code "49") (name "Net-(IC5-OUT)") (class "Default")
      (node (ref "IC5") (pin "14") (pinfunction "OUT_14") (pintype "bidirectional"))
      (node (ref "R16") (pin "2") (pinfunction "2_2") (pintype "passive"))
      (node (ref "RR17") (pin "2") (pinfunction "2_2") (pintype "passive"))
    )
    (net (code "50") (name "Net-(IC6-VIN)") (class "Default")
      (node (ref "C10") (pin "+") (pinfunction "+_+") (pintype "passive"))
      (node (ref "C7") (pin "2") (pinfunction "2_2") (pintype "passive"))
      (node (ref "IC6") (pin "3") (pinfunction "VIN_3") (pintype "input"))
      (node (ref "L1") (pin "1") (pinfunction "2_1") (pintype "passive"))
    )
    (net (code "51") (name "Net-(IC8-PadAC1)") (class "Default")
      (node (ref "IC8") (pin "AC1") (pinfunction "AC1_AC1") (pintype "passive"))
      (node (ref "U$2") (pin "PIN") (pinfunction "PIN_PIN") (pintype "bidirectional"))
    )
    (net (code "52") (name "Net-(IC8-PadAC2)") (class "Default")
      (node (ref "IC8") (pin "AC2") (pinfunction "AC2_AC2") (pintype "passive"))
      (node (ref "U$2") (pin "BARREL") (pinfunction "BARREL_BARREL") (pintype "bidirectional"))
    )
    (net (code "53") (name "Net-(IC9-VB)") (class "Default")
      (node (ref "IC9") (pin "7") (pinfunction "VB_7") (pintype "passive"))
      (node (ref "R20") (pin "2") (pinfunction "2_2") (pintype "passive"))
    )
    (net (code "54") (name "Net-(L1-1)") (class "Default")
      (node (ref "C11") (pin "+") (pinfunction "+_+") (pintype "passive"))
      (node (ref "IC8") (pin "+") (pinfunction "+_+") (pintype "passive"))
      (node (ref "L1") (pin "2") (pinfunction "1_2") (pintype "passive"))
    )
    (net (code "55") (name "Net-(LED1-PadA)") (class "Default")
      (node (ref "LED1") (pin "A") (pinfunction "A_A") (pintype "passive"))
      (node (ref "R28") (pin "2") (pinfunction "2_2") (pintype "passive"))
    )
    (net (code "56") (name "Net-(LED2-PadA)") (class "Default")
      (node (ref "LED2") (pin "A") (pinfunction "A_A") (pintype "passive"))
      (node (ref "R27") (pin "2") (pinfunction "2_2") (pintype "passive"))
    )
    (net (code "57") (name "Net-(LED3-PadA)") (class "Default")
      (node (ref "LED3") (pin "A") (pinfunction "A_A") (pintype "passive"))
      (node (ref "R26") (pin "2") (pinfunction "2_2") (pintype "passive"))
    )
    (net (code "58") (name "Net-(LED4-PadA)") (class "Default")
      (node (ref "LED4") (pin "A") (pinfunction "A_A") (pintype "passive"))
      (node (ref "R25") (pin "2") (pinfunction "2_2") (pintype "passive"))
    )
    (net (code "59") (name "Net-(LED5-PadA)") (class "Default")
      (node (ref "LED5") (pin "A") (pinfunction "A_A") (pintype "passive"))
      (node (ref "R13") (pin "2") (pinfunction "2_2") (pintype "passive"))
    )
    (net (code "60") (name "Net-(LED6-PadA)") (class "Default")
      (node (ref "LED6") (pin "A") (pinfunction "A_A") (pintype "passive"))
      (node (ref "R12") (pin "2") (pinfunction "2_2") (pintype "passive"))
    )
    (net (code "61") (name "Net-(LED7-PadA)") (class "Default")
      (node (ref "LED7") (pin "A") (pinfunction "A_A") (pintype "passive"))
      (node (ref "R11") (pin "2") (pinfunction "2_2") (pintype "passive"))
    )
    (net (code "62") (name "Net-(LED8-PadA)") (class "Default")
      (node (ref "LED8") (pin "A") (pinfunction "A_A") (pintype "passive"))
      (node (ref "R10") (pin "2") (pinfunction "2_2") (pintype "passive"))
    )
    (net (code "63") (name "Net-(LED9-C)") (class "Default")
      (node (ref "LED9") (pin "K") (pinfunction "C_K") (pintype "passive"))
      (node (ref "R2") (pin "2") (pinfunction "2_2") (pintype "passive"))
    )
    (net (code "64") (name "Net-(LED10-PadA)") (class "Default")
      (node (ref "LED10") (pin "A") (pinfunction "A_A") (pintype "passive"))
      (node (ref "R1") (pin "2") (pinfunction "2_2") (pintype "passive"))
    )
    (net (code "65") (name "Net-(MIDI-Pad4)") (class "Default")
      (node (ref "MIDI") (pin "4") (pinfunction "4_4") (pintype "bidirectional"))
      (node (ref "MIDI_IN") (pin "4") (pinfunction "4_4") (pintype "passive"))
      (node (ref "R21") (pin "2") (pinfunction "2_2") (pintype "passive"))
    )
    (net (code "66") (name "Net-(OUTA-PadPIN)") (class "Default")
      (node (ref "OUTA") (pin "PIN") (pinfunction "PIN_PIN") (pintype "bidirectional"))
      (node (ref "R16") (pin "1") (pinfunction "1_1") (pintype "passive"))
    )
    (net (code "67") (name "Net-(OUTB-PadPIN)") (class "Default")
      (node (ref "OUTB") (pin "PIN") (pinfunction "PIN_PIN") (pintype "bidirectional"))
      (node (ref "R4") (pin "1") (pinfunction "1_1") (pintype "passive"))
    )
    (net (code "68") (name "unconnected-(IC1-NC1-Pad3)") (class "Default")
      (node (ref "IC1") (pin "3") (pinfunction "NC1_3") (pintype "bidirectional"))
    )
    (net (code "69") (name "unconnected-(IC1-NC2-Pad6)") (class "Default")
      (node (ref "IC1") (pin "6") (pinfunction "NC2_6") (pintype "bidirectional"))
    )
    (net (code "70") (name "unconnected-(IC1-NC3-Pad9)") (class "Default")
      (node (ref "IC1") (pin "9") (pinfunction "NC3_9") (pintype "bidirectional"))
    )
    (net (code "71") (name "unconnected-(IC5-NC1-Pad3)") (class "Default")
      (node (ref "IC5") (pin "3") (pinfunction "NC1_3") (pintype "bidirectional"))
    )
    (net (code "72") (name "unconnected-(IC5-NC2-Pad6)") (class "Default")
      (node (ref "IC5") (pin "6") (pinfunction "NC2_6") (pintype "bidirectional"))
    )
    (net (code "73") (name "unconnected-(IC5-NC3-Pad9)") (class "Default")
      (node (ref "IC5") (pin "9") (pinfunction "NC3_9") (pintype "bidirectional"))
    )
    (net (code "74") (name "unconnected-(IC7A-QA-Pad15)") (class "Default")
      (node (ref "IC7") (pin "15") (pinfunction "QA_15") (pintype "tri_state"))
    )
    (net (code "75") (name "unconnected-(IC7A-QB-Pad1)") (class "Default")
      (node (ref "IC7") (pin "1") (pinfunction "QB_1") (pintype "tri_state"))
    )
    (net (code "76") (name "unconnected-(IC7A-QC-Pad2)") (class "Default")
      (node (ref "IC7") (pin "2") (pinfunction "QC_2") (pintype "tri_state"))
    )
    (net (code "77") (name "unconnected-(IC7A-QD-Pad3)") (class "Default")
      (node (ref "IC7") (pin "3") (pinfunction "QD_3") (pintype "tri_state"))
    )
    (net (code "78") (name "unconnected-(IC7A-QH*-Pad9)") (class "Default")
      (node (ref "IC7") (pin "9") (pinfunction "QH*_9") (pintype "tri_state"))
    )
    (net (code "79") (name "unconnected-(ICSP-LVP-Pad6)") (class "Default")
      (node (ref "ICSP") (pin "6") (pinfunction "LVP_6") (pintype "bidirectional"))
    )
    (net (code "80") (name "unconnected-(INB1-R2-PadP$3)") (class "Default")
      (node (ref "INB1") (pin "P$3") (pinfunction "R2_P$3") (pintype "bidirectional"))
    )
    (net (code "81") (name "unconnected-(INB1-R3-PadP$4)") (class "Default")
      (node (ref "INB1") (pin "P$4") (pinfunction "R3_P$4") (pintype "bidirectional"))
    )
    (net (code "82") (name "unconnected-(INB1-R4-PadP$5)") (class "Default")
      (node (ref "INB1") (pin "P$5") (pinfunction "R4_P$5") (pintype "bidirectional"))
    )
    (net (code "83") (name "unconnected-(MIDI-Pad2)") (class "Default")
      (node (ref "MIDI") (pin "2") (pinfunction "2_2") (pintype "bidirectional"))
    )
    (net (code "84") (name "unconnected-(MIDI_IN-Pad1)") (class "Default")
      (node (ref "MIDI_IN") (pin "1") (pinfunction "1_1") (pintype "passive"))
    )
    (net (code "85") (name "unconnected-(MIDI_IN-Pad2)") (class "Default")
      (node (ref "MIDI_IN") (pin "2") (pinfunction "2_2") (pintype "passive"))
    )
    (net (code "86") (name "unconnected-(MIDI_IN-Pad3)") (class "Default")
      (node (ref "MIDI_IN") (pin "3") (pinfunction "3_3") (pintype "passive"))
    )
    (net (code "87") (name "unconnected-(U$2-PadNC)") (class "Default")
      (node (ref "U$2") (pin "NC") (pinfunction "NC_NC") (pintype "bidirectional"))
    )
  )
)
